# NC1-3-Top.net
KiCad netlist of a schematic drawn in Altium Designer
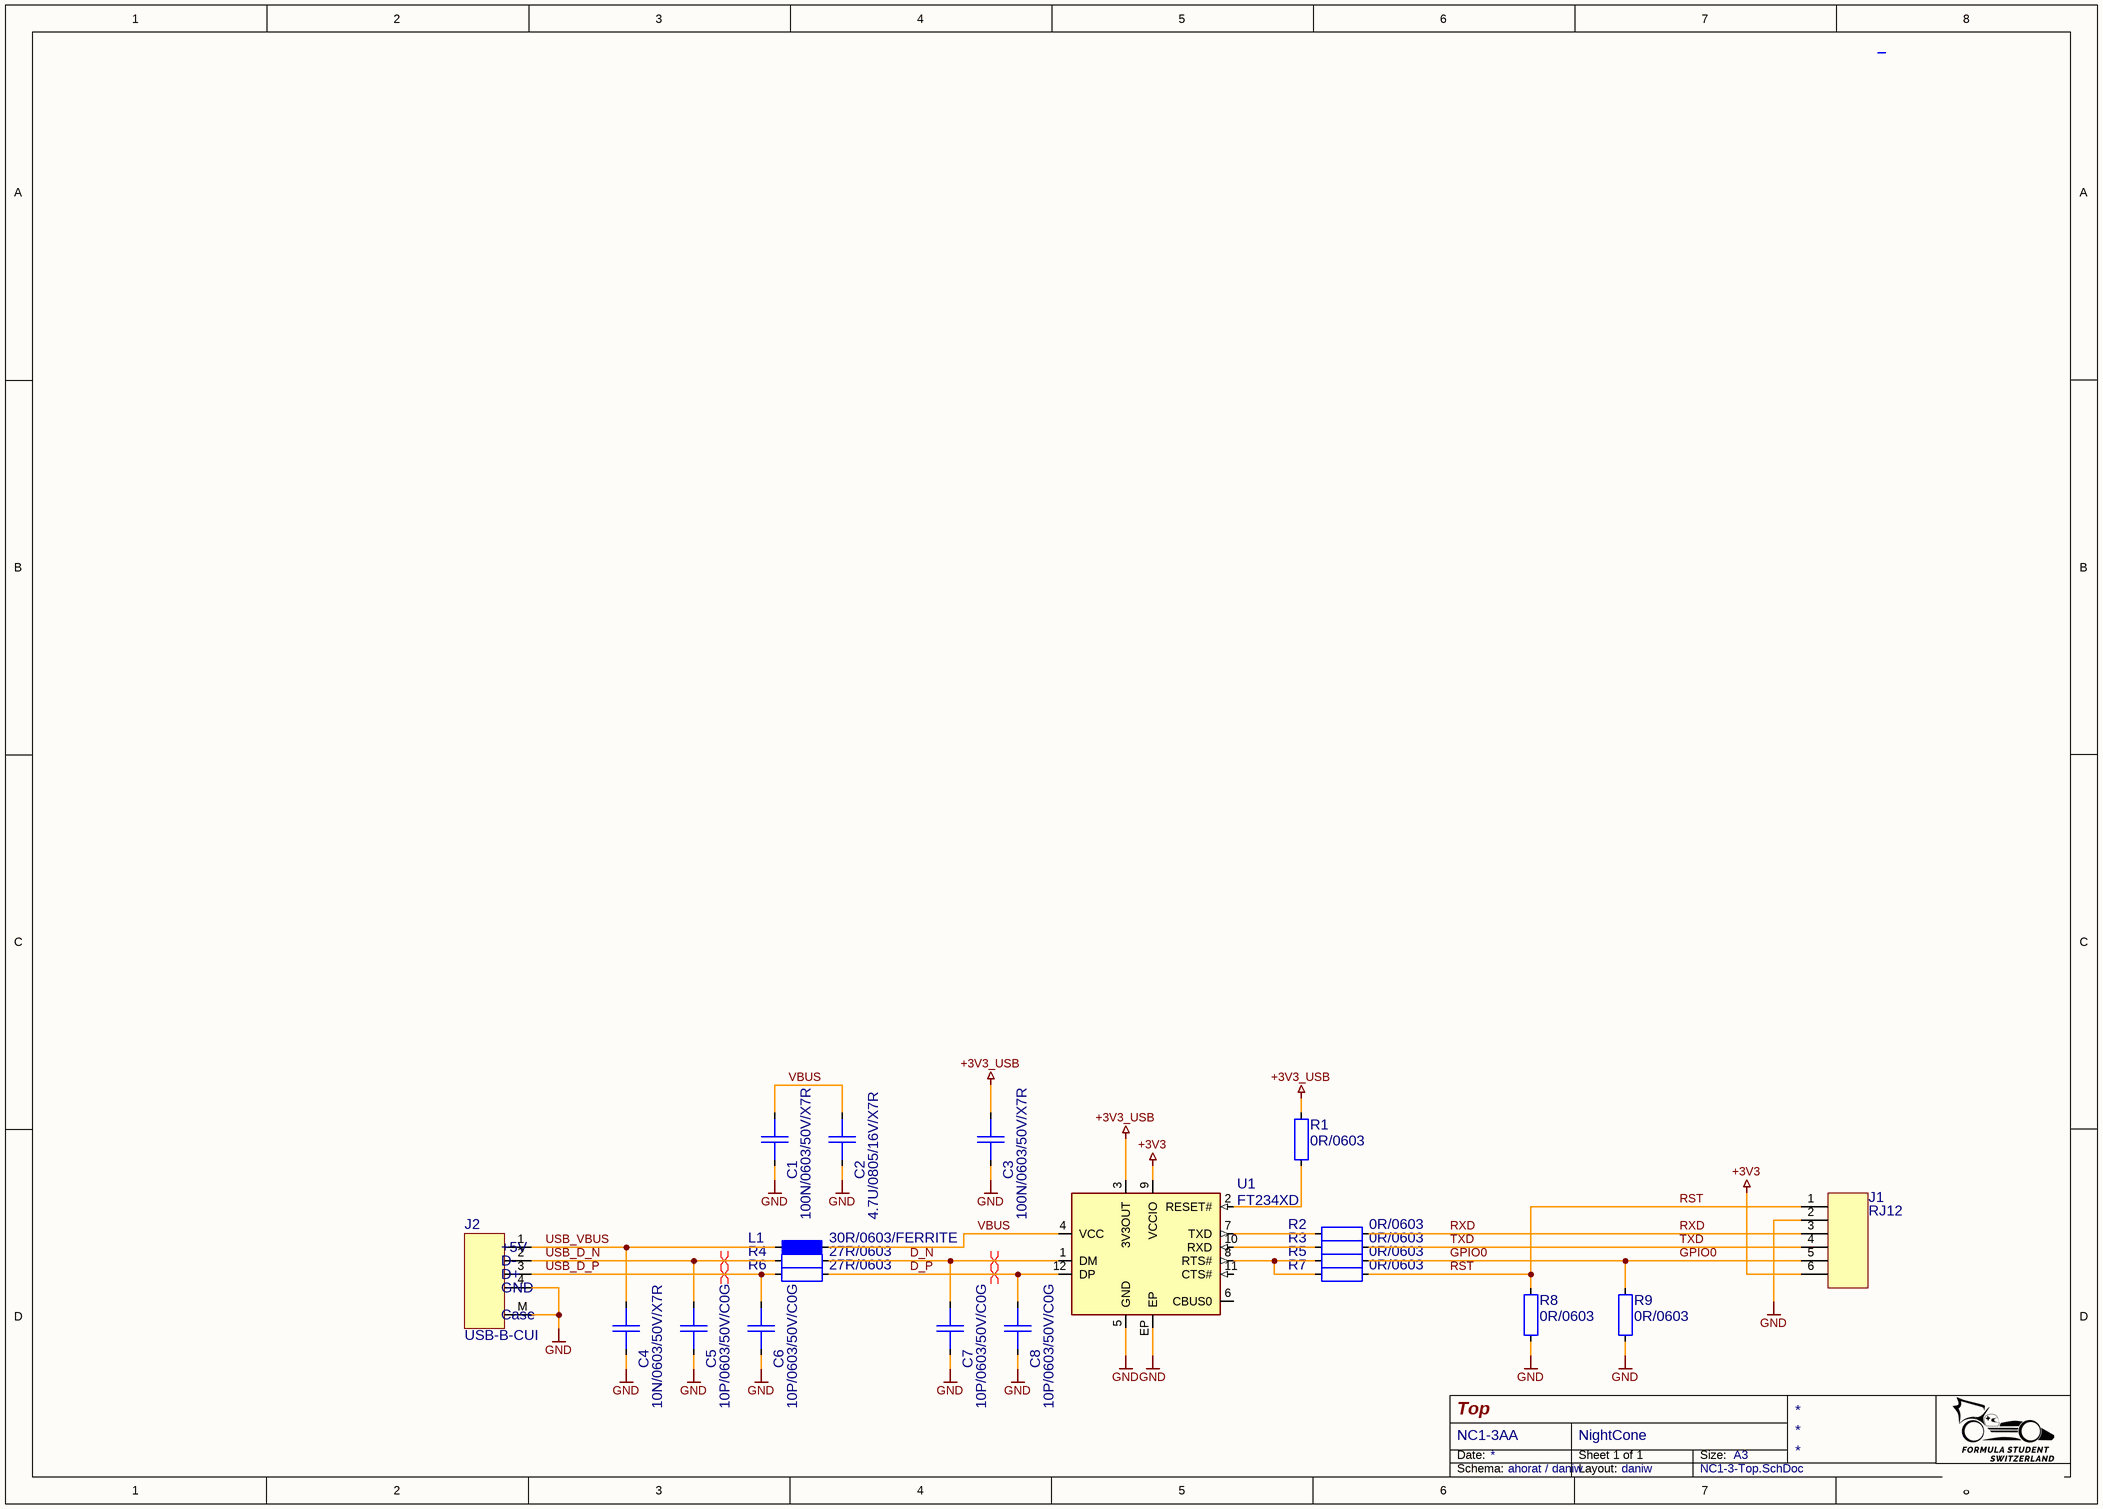
[diagram p0: NC1-3-Top.SchDoc]

(export (version "E")
  (design (tool "Eeschema 10.0.6"))
  (components
    (comp (ref "C1")
      (value "100N/0603/50V/X7R")
      (footprint "CAP0603_X7R")
      (description "CAP SM 0603 100nF 50V X7R")
      (fields (field (name "MANUFACTURER") "GENERIC"))
      (libsource (lib "daniw_altium_lib") (part "C"))
    )
    (comp (ref "C2")
      (value "4.7U/0805/16V/X7R")
      (footprint "CAP0805_X7R")
      (description "CAP SM 0805 4.7uF 16V X7R")
      (fields (field (name "MANUFACTURER") "GENERIC"))
      (libsource (lib "daniw_altium_lib") (part "C"))
    )
    (comp (ref "C3")
      (value "100N/0603/50V/X7R")
      (footprint "CAP0603_X7R")
      (description "CAP SM 0603 100nF 50V X7R")
      (fields (field (name "MANUFACTURER") "GENERIC"))
      (libsource (lib "daniw_altium_lib") (part "C"))
    )
    (comp (ref "C4")
      (value "10N/0603/50V/X7R")
      (footprint "CAP0603_X7R")
      (description "CAP SM 0603 10nF 50V X7R")
      (fields (field (name "MANUFACTURER") "GENERIC"))
      (libsource (lib "daniw_altium_lib") (part "C"))
    )
    (comp (ref "C5")
      (value "10P/0603/50V/C0G")
      (footprint "CAP0603_C0G")
      (description "CAP SM 0603 10pF 50V C0G")
      (fields (field (name "MANUFACTURER") "GENERIC"))
      (libsource (lib "daniw_altium_lib") (part "C"))
    )
    (comp (ref "C6")
      (value "10P/0603/50V/C0G")
      (footprint "CAP0603_C0G")
      (description "CAP SM 0603 10pF 50V C0G")
      (fields (field (name "MANUFACTURER") "GENERIC"))
      (libsource (lib "daniw_altium_lib") (part "C"))
    )
    (comp (ref "C7")
      (value "10P/0603/50V/C0G")
      (footprint "CAP0603_C0G")
      (description "CAP SM 0603 10pF 50V C0G")
      (fields (field (name "MANUFACTURER") "GENERIC"))
      (libsource (lib "daniw_altium_lib") (part "C"))
    )
    (comp (ref "C8")
      (value "10P/0603/50V/C0G")
      (footprint "CAP0603_C0G")
      (description "CAP SM 0603 10pF 50V C0G")
      (fields (field (name "MANUFACTURER") "GENERIC"))
      (libsource (lib "daniw_altium_lib") (part "C"))
    )
    (comp (ref "J1")
      (value "RJ12")
      (footprint "RJ12-PULSE-E5566-Q0LK22-L")
      (description "RJ12 Pulse E5566-Q0LK22-L")
      (fields (field (name "PART NUMBER") "RJ12-PULSE-E5566-Q0LK22-L") (field (name "MANUFACTURER") "Pulse"))
      (libsource (lib "daniw_altium_lib") (part "CON6"))
    )
    (comp (ref "J2")
      (value "USB-B-CUI")
      (footprint "USB-B_CUI_UJ2-BH-TH")
      (description "USB-B CUI UJ2-BH-TH")
      (fields (field (name "MANUFACTURER") "CUI"))
      (libsource (lib "daniw_altium_lib") (part "CON4-M_USB"))
    )
    (comp (ref "L1")
      (value "30R/0603/FERRITE")
      (footprint "FB0603")
      (description "30R@100MHz 5A 0603 Ferrite")
      (fields (field (name "MANUFACTURER") "GENERIC"))
      (libsource (lib "daniw_altium_lib") (part "Ferrite"))
    )
    (comp (ref "R1")
      (value "0R/0603")
      (footprint "R0603-0.40-WW")
      (description "RES SM 0603 0R")
      (fields (field (name "MANUFACTURER") "GENERIC"))
      (libsource (lib "daniw_altium_lib") (part "R"))
    )
    (comp (ref "R2")
      (value "0R/0603")
      (footprint "R0603-0.40-WW")
      (description "RES SM 0603 0R")
      (fields (field (name "MANUFACTURER") "GENERIC"))
      (libsource (lib "daniw_altium_lib") (part "R"))
    )
    (comp (ref "R3")
      (value "0R/0603")
      (footprint "R0603-0.40-WW")
      (description "RES SM 0603 0R")
      (fields (field (name "MANUFACTURER") "GENERIC"))
      (libsource (lib "daniw_altium_lib") (part "R"))
    )
    (comp (ref "R4")
      (value "27R/0603")
      (footprint "R0603-0.40-WW")
      (description "RES SM 0603 27R")
      (fields (field (name "MANUFACTURER") "GENERIC"))
      (libsource (lib "daniw_altium_lib") (part "R"))
    )
    (comp (ref "R5")
      (value "0R/0603")
      (footprint "R0603-0.40-WW")
      (description "RES SM 0603 0R")
      (fields (field (name "MANUFACTURER") "GENERIC"))
      (libsource (lib "daniw_altium_lib") (part "R"))
    )
    (comp (ref "R6")
      (value "27R/0603")
      (footprint "R0603-0.40-WW")
      (description "RES SM 0603 27R")
      (fields (field (name "MANUFACTURER") "GENERIC"))
      (libsource (lib "daniw_altium_lib") (part "R"))
    )
    (comp (ref "R7")
      (value "0R/0603")
      (footprint "R0603-0.40-WW")
      (description "RES SM 0603 0R")
      (fields (field (name "MANUFACTURER") "GENERIC"))
      (libsource (lib "daniw_altium_lib") (part "R"))
    )
    (comp (ref "R8")
      (value "0R/0603")
      (footprint "R0603-0.40-WW")
      (description "RES SM 0603 0R")
      (fields (field (name "MANUFACTURER") "GENERIC"))
      (libsource (lib "daniw_altium_lib") (part "R"))
    )
    (comp (ref "R9")
      (value "0R/0603")
      (footprint "R0603-0.40-WW")
      (description "RES SM 0603 0R")
      (fields (field (name "MANUFACTURER") "GENERIC"))
      (libsource (lib "daniw_altium_lib") (part "R"))
    )
    (comp (ref "U1")
      (value "FT234XD")
      (footprint "DFN045P300X300X080-12-EP160X250")
      (description "FT234XD USB TO BASIC UART IC")
      (fields (field (name "MANUFACTURER") "FTDI"))
      (libsource (lib "daniw_altium_lib") (part "FT234XD"))
    )
  )
  (nets
    (net (code "1") (name "+3V3") (class "Default")
      (node (ref "J1") (pin "6") (pintype "passive"))
      (node (ref "U1") (pin "9") (pinfunction "VCCIO_9") (pintype "passive"))
    )
    (net (code "2") (name "+3V3_USB") (class "Default")
      (node (ref "C3") (pin "1") (pinfunction "1_1") (pintype "passive"))
      (node (ref "R1") (pin "1") (pinfunction "1_1") (pintype "passive"))
      (node (ref "U1") (pin "3") (pinfunction "3V3OUT_3") (pintype "passive"))
    )
    (net (code "3") (name "/D_N") (class "Default")
      (node (ref "C7") (pin "1") (pinfunction "1_1") (pintype "passive"))
      (node (ref "R4") (pin "2") (pinfunction "2_2") (pintype "passive"))
      (node (ref "U1") (pin "1") (pinfunction "DM_1") (pintype "bidirectional"))
    )
    (net (code "4") (name "/D_P") (class "Default")
      (node (ref "C8") (pin "1") (pinfunction "1_1") (pintype "passive"))
      (node (ref "R6") (pin "2") (pinfunction "2_2") (pintype "passive"))
      (node (ref "U1") (pin "12") (pinfunction "DP_12") (pintype "bidirectional"))
    )
    (net (code "5") (name "/GPIO0") (class "Default")
      (node (ref "J1") (pin "5") (pintype "passive"))
      (node (ref "R5") (pin "2") (pinfunction "2_2") (pintype "passive"))
      (node (ref "R9") (pin "2") (pinfunction "2_2") (pintype "passive"))
    )
    (net (code "6") (name "/RST") (class "Default")
      (node (ref "J1") (pin "1") (pintype "passive"))
      (node (ref "R7") (pin "2") (pinfunction "2_2") (pintype "passive"))
      (node (ref "R8") (pin "2") (pinfunction "2_2") (pintype "passive"))
    )
    (net (code "7") (name "/RXD") (class "Default")
      (node (ref "J1") (pin "3") (pintype "passive"))
      (node (ref "R2") (pin "2") (pinfunction "2_2") (pintype "passive"))
    )
    (net (code "8") (name "/TXD") (class "Default")
      (node (ref "J1") (pin "4") (pintype "passive"))
      (node (ref "R3") (pin "2") (pinfunction "2_2") (pintype "passive"))
    )
    (net (code "9") (name "/USB_D_N") (class "Default")
      (node (ref "C5") (pin "1") (pinfunction "1_1") (pintype "passive"))
      (node (ref "J2") (pin "2") (pintype "passive"))
      (node (ref "R4") (pin "1") (pinfunction "1_1") (pintype "passive"))
    )
    (net (code "10") (name "/USB_D_P") (class "Default")
      (node (ref "C6") (pin "1") (pinfunction "1_1") (pintype "passive"))
      (node (ref "J2") (pin "3") (pintype "passive"))
      (node (ref "R6") (pin "1") (pinfunction "1_1") (pintype "passive"))
    )
    (net (code "11") (name "/USB_VBUS") (class "Default")
      (node (ref "C4") (pin "1") (pinfunction "1_1") (pintype "passive"))
      (node (ref "J2") (pin "1") (pintype "passive"))
      (node (ref "L1") (pin "1") (pinfunction "1_1") (pintype "passive"))
    )
    (net (code "12") (name "/VBUS") (class "Default")
      (node (ref "C1") (pin "1") (pinfunction "1_1") (pintype "passive"))
      (node (ref "C2") (pin "1") (pinfunction "1_1") (pintype "passive"))
      (node (ref "L1") (pin "2") (pinfunction "2_2") (pintype "passive"))
      (node (ref "U1") (pin "4") (pinfunction "VCC_4") (pintype "passive"))
    )
    (net (code "13") (name "GND") (class "Default")
      (node (ref "C1") (pin "2") (pinfunction "2_2") (pintype "passive"))
      (node (ref "C2") (pin "2") (pinfunction "2_2") (pintype "passive"))
      (node (ref "C3") (pin "2") (pinfunction "2_2") (pintype "passive"))
      (node (ref "C4") (pin "2") (pinfunction "2_2") (pintype "passive"))
      (node (ref "C5") (pin "2") (pinfunction "2_2") (pintype "passive"))
      (node (ref "C6") (pin "2") (pinfunction "2_2") (pintype "passive"))
      (node (ref "C7") (pin "2") (pinfunction "2_2") (pintype "passive"))
      (node (ref "C8") (pin "2") (pinfunction "2_2") (pintype "passive"))
      (node (ref "J1") (pin "2") (pintype "passive"))
      (node (ref "J2") (pin "4") (pintype "passive"))
      (node (ref "J2") (pin "M") (pintype "passive"))
      (node (ref "R8") (pin "1") (pinfunction "1_1") (pintype "passive"))
      (node (ref "R9") (pin "1") (pinfunction "1_1") (pintype "passive"))
      (node (ref "U1") (pin "5") (pinfunction "GND_5") (pintype "passive"))
      (node (ref "U1") (pin "EP") (pinfunction "EP_EP") (pintype "passive"))
    )
    (net (code "14") (name "Net-(U1-RESET#)") (class "Default")
      (node (ref "R1") (pin "2") (pinfunction "2_2") (pintype "passive"))
      (node (ref "U1") (pin "2") (pinfunction "RESET#_2") (pintype "input"))
    )
    (net (code "15") (name "Net-(U1-RTS#)") (class "Default")
      (node (ref "R5") (pin "1") (pinfunction "1_1") (pintype "passive"))
      (node (ref "R7") (pin "1") (pinfunction "1_1") (pintype "passive"))
      (node (ref "U1") (pin "8") (pinfunction "RTS#_8") (pintype "output"))
    )
    (net (code "16") (name "Net-(U1-RXD)") (class "Default")
      (node (ref "R3") (pin "1") (pinfunction "1_1") (pintype "passive"))
      (node (ref "U1") (pin "10") (pinfunction "RXD_10") (pintype "input"))
    )
    (net (code "17") (name "Net-(U1-TXD)") (class "Default")
      (node (ref "R2") (pin "1") (pinfunction "1_1") (pintype "passive"))
      (node (ref "U1") (pin "7") (pinfunction "TXD_7") (pintype "output"))
    )
    (net (code "18") (name "unconnected-(U1-CBUS0-Pad6)") (class "Default")
      (node (ref "U1") (pin "6") (pinfunction "CBUS0_6") (pintype "bidirectional"))
    )
    (net (code "19") (name "unconnected-(U1-CTS#-Pad11)") (class "Default")
      (node (ref "U1") (pin "11") (pinfunction "CTS#_11") (pintype "input"))
    )
  )
)
